# SCH_usb-hub_2025-07-15.net
KiCad netlist of a schematic drawn in EasyEDA
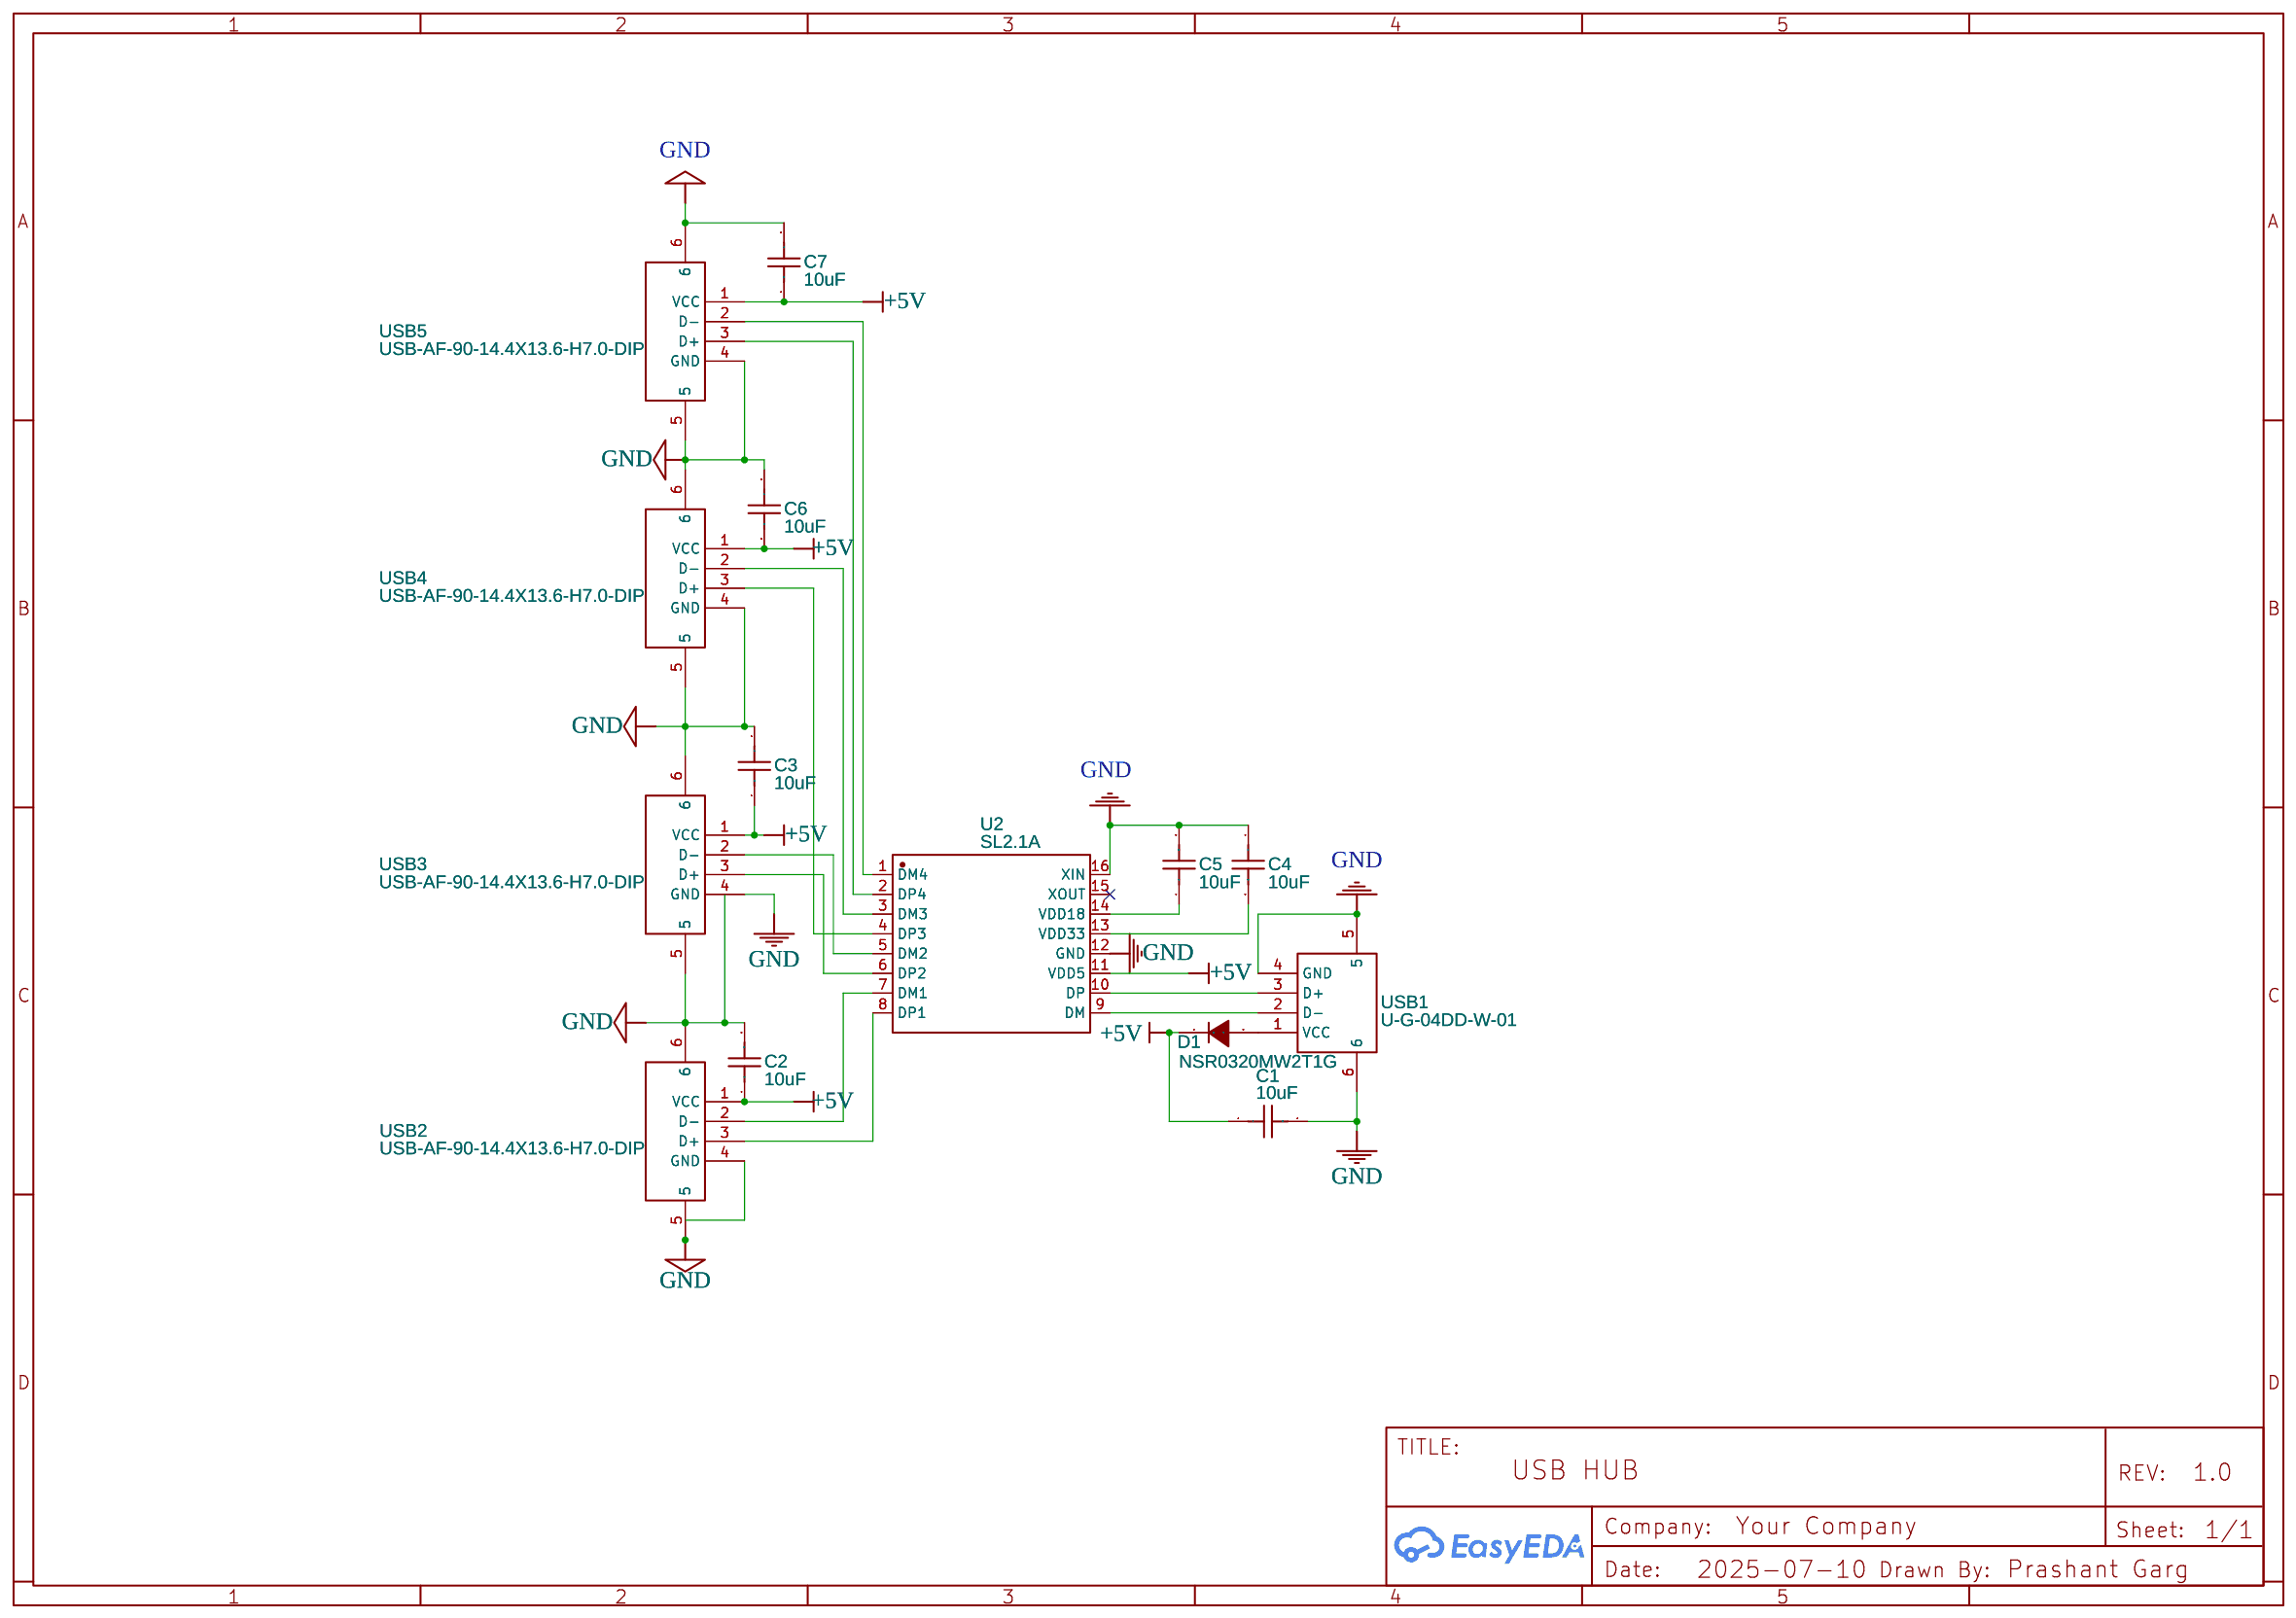
[diagram p0: schematic sheet]

(export (version "E")
  (design (tool "Eeschema 10.0.6"))
  (components
    (comp (ref "C1")
      (value "10uF")
      (fields
        (field (name "Manufacturer Part") "CL10A106KP8NNNC")
        (field (name "Manufacturer") "SAMSUNG(三星)")
      )
      (libsource (lib "") (part "CL10A106KP8NNNC_1"))
    )
    (comp (ref "C2")
      (value "10uF")
      (fields
        (field (name "Manufacturer Part") "CL10A106KP8NNNC")
        (field (name "Manufacturer") "SAMSUNG(三星)")
      )
      (libsource (lib "") (part "CL10A106KP8NNNC"))
    )
    (comp (ref "C3")
      (value "10uF")
      (fields
        (field (name "Manufacturer Part") "CL10A106KP8NNNC")
        (field (name "Manufacturer") "SAMSUNG(三星)")
      )
      (libsource (lib "") (part "CL10A106KP8NNNC"))
    )
    (comp (ref "C4")
      (value "10uF")
      (fields
        (field (name "Manufacturer Part") "CL10A106KP8NNNC")
        (field (name "Manufacturer") "SAMSUNG(三星)")
      )
      (libsource (lib "") (part "CL10A106KP8NNNC_2"))
    )
    (comp (ref "C5")
      (value "10uF")
      (fields
        (field (name "Manufacturer Part") "CL10A106KP8NNNC")
        (field (name "Manufacturer") "SAMSUNG(三星)")
      )
      (libsource (lib "") (part "CL10A106KP8NNNC"))
    )
    (comp (ref "C6")
      (value "10uF")
      (fields
        (field (name "Manufacturer Part") "CL10A106KP8NNNC")
        (field (name "Manufacturer") "SAMSUNG(三星)")
      )
      (libsource (lib "") (part "CL10A106KP8NNNC"))
    )
    (comp (ref "C7")
      (value "10uF")
      (fields
        (field (name "Manufacturer Part") "CL10A106KP8NNNC")
        (field (name "Manufacturer") "SAMSUNG(三星)")
      )
      (libsource (lib "") (part "CL10A106KP8NNNC"))
    )
    (comp (ref "D1")
      (value "NSR0320MW2T1G")
      (fields (field (name "Manufacturer") "onsemi(安森美)"))
      (libsource (lib "") (part "NSR0320MW2T1G"))
    )
    (comp (ref "U2")
      (value "SL2.1A")
      (fields (field (name "Manufacturer") "CoreChips(和芯润德)"))
      (libsource (lib "") (part "SL2.1A"))
    )
    (comp (ref "USB1")
      (value "U-G-04DD-W-01")
      (fields (field (name "Manufacturer Part") "U-G-O4DD-W-1") (field (name "Manufacturer") "韩国韩荣"))
      (libsource (lib "") (part "U-G-04DD-W-01"))
    )
    (comp (ref "USB2")
      (value "USB-AF-90-14.4X13.6-H7.0-DIP")
      (fields (field (name "Manufacturer Part") "903-131A1011D10100") (field (name "Manufacturer") "精拓金"))
      (libsource (lib "") (part "USB-AF-90-14.4X13.6-H7.0-DIP"))
    )
    (comp (ref "USB3")
      (value "USB-AF-90-14.4X13.6-H7.0-DIP")
      (fields (field (name "Manufacturer Part") "903-131A1011D10100") (field (name "Manufacturer") "精拓金"))
      (libsource (lib "") (part "USB-AF-90-14.4X13.6-H7.0-DIP"))
    )
    (comp (ref "USB4")
      (value "USB-AF-90-14.4X13.6-H7.0-DIP")
      (fields (field (name "Manufacturer Part") "903-131A1011D10100") (field (name "Manufacturer") "精拓金"))
      (libsource (lib "") (part "USB-AF-90-14.4X13.6-H7.0-DIP"))
    )
    (comp (ref "USB5")
      (value "USB-AF-90-14.4X13.6-H7.0-DIP")
      (fields (field (name "Manufacturer Part") "903-131A1011D10100") (field (name "Manufacturer") "精拓金"))
      (libsource (lib "") (part "USB-AF-90-14.4X13.6-H7.0-DIP"))
    )
  )
  (nets
    (net (code "1") (name "+5V") (class "Default")
      (node (ref "C1") (pin "1") (pinfunction "1_1") (pintype "unspecified"))
      (node (ref "C2") (pin "1") (pinfunction "1_1") (pintype "unspecified"))
      (node (ref "C3") (pin "1") (pinfunction "1_1") (pintype "unspecified"))
      (node (ref "C6") (pin "1") (pinfunction "1_1") (pintype "unspecified"))
      (node (ref "C7") (pin "1") (pinfunction "1_1") (pintype "unspecified"))
      (node (ref "D1") (pin "1") (pinfunction "C_1") (pintype "unspecified"))
      (node (ref "U2") (pin "11") (pinfunction "VDD5_11") (pintype "unspecified"))
      (node (ref "USB2") (pin "1") (pinfunction "VCC_1") (pintype "unspecified"))
      (node (ref "USB3") (pin "1") (pinfunction "VCC_1") (pintype "unspecified"))
      (node (ref "USB4") (pin "1") (pinfunction "VCC_1") (pintype "unspecified"))
      (node (ref "USB5") (pin "1") (pinfunction "VCC_1") (pintype "unspecified"))
    )
    (net (code "2") (name "GND") (class "Default")
      (node (ref "C1") (pin "2") (pinfunction "2_2") (pintype "unspecified"))
      (node (ref "C2") (pin "2") (pinfunction "2_2") (pintype "unspecified"))
      (node (ref "C3") (pin "2") (pinfunction "2_2") (pintype "unspecified"))
      (node (ref "C4") (pin "1") (pinfunction "1_1") (pintype "unspecified"))
      (node (ref "C5") (pin "2") (pinfunction "2_2") (pintype "unspecified"))
      (node (ref "C6") (pin "2") (pinfunction "2_2") (pintype "unspecified"))
      (node (ref "C7") (pin "2") (pinfunction "2_2") (pintype "unspecified"))
      (node (ref "U2") (pin "12") (pinfunction "GND_12") (pintype "unspecified"))
      (node (ref "U2") (pin "16") (pinfunction "XIN_16") (pintype "unspecified"))
      (node (ref "USB1") (pin "4") (pinfunction "GND_4") (pintype "unspecified"))
      (node (ref "USB1") (pin "5") (pinfunction "5_5") (pintype "unspecified"))
      (node (ref "USB1") (pin "6") (pinfunction "6_6") (pintype "unspecified"))
      (node (ref "USB2") (pin "4") (pinfunction "GND_4") (pintype "unspecified"))
      (node (ref "USB2") (pin "5") (pinfunction "5_5") (pintype "unspecified"))
      (node (ref "USB2") (pin "6") (pinfunction "6_6") (pintype "unspecified"))
      (node (ref "USB3") (pin "4") (pinfunction "GND_4") (pintype "unspecified"))
      (node (ref "USB3") (pin "5") (pinfunction "5_5") (pintype "unspecified"))
      (node (ref "USB3") (pin "6") (pinfunction "6_6") (pintype "unspecified"))
      (node (ref "USB4") (pin "4") (pinfunction "GND_4") (pintype "unspecified"))
      (node (ref "USB4") (pin "5") (pinfunction "5_5") (pintype "unspecified"))
      (node (ref "USB4") (pin "6") (pinfunction "6_6") (pintype "unspecified"))
      (node (ref "USB5") (pin "4") (pinfunction "GND_4") (pintype "unspecified"))
      (node (ref "USB5") (pin "5") (pinfunction "5_5") (pintype "unspecified"))
      (node (ref "USB5") (pin "6") (pinfunction "6_6") (pintype "unspecified"))
    )
    (net (code "3") (name "Net-(D1-A)") (class "Default")
      (node (ref "D1") (pin "2") (pinfunction "A_2") (pintype "unspecified"))
      (node (ref "USB1") (pin "1") (pinfunction "VCC_1") (pintype "unspecified"))
    )
    (net (code "4") (name "Net-(U2-DM)") (class "Default")
      (node (ref "U2") (pin "9") (pinfunction "DM_9") (pintype "unspecified"))
      (node (ref "USB1") (pin "2") (pinfunction "D-_2") (pintype "unspecified"))
    )
    (net (code "5") (name "Net-(U2-DM1)") (class "Default")
      (node (ref "U2") (pin "7") (pinfunction "DM1_7") (pintype "unspecified"))
      (node (ref "USB2") (pin "2") (pinfunction "D-_2") (pintype "unspecified"))
    )
    (net (code "6") (name "Net-(U2-DM2)") (class "Default")
      (node (ref "U2") (pin "5") (pinfunction "DM2_5") (pintype "unspecified"))
      (node (ref "USB3") (pin "2") (pinfunction "D-_2") (pintype "unspecified"))
    )
    (net (code "7") (name "Net-(U2-DM3)") (class "Default")
      (node (ref "U2") (pin "3") (pinfunction "DM3_3") (pintype "unspecified"))
      (node (ref "USB4") (pin "2") (pinfunction "D-_2") (pintype "unspecified"))
    )
    (net (code "8") (name "Net-(U2-DM4)") (class "Default")
      (node (ref "U2") (pin "1") (pinfunction "DM4_1") (pintype "unspecified"))
      (node (ref "USB5") (pin "2") (pinfunction "D-_2") (pintype "unspecified"))
    )
    (net (code "9") (name "Net-(U2-DP)") (class "Default")
      (node (ref "U2") (pin "10") (pinfunction "DP_10") (pintype "unspecified"))
      (node (ref "USB1") (pin "3") (pinfunction "D+_3") (pintype "unspecified"))
    )
    (net (code "10") (name "Net-(U2-DP1)") (class "Default")
      (node (ref "U2") (pin "8") (pinfunction "DP1_8") (pintype "unspecified"))
      (node (ref "USB2") (pin "3") (pinfunction "D+_3") (pintype "unspecified"))
    )
    (net (code "11") (name "Net-(U2-DP2)") (class "Default")
      (node (ref "U2") (pin "6") (pinfunction "DP2_6") (pintype "unspecified"))
      (node (ref "USB3") (pin "3") (pinfunction "D+_3") (pintype "unspecified"))
    )
    (net (code "12") (name "Net-(U2-DP3)") (class "Default")
      (node (ref "U2") (pin "4") (pinfunction "DP3_4") (pintype "unspecified"))
      (node (ref "USB4") (pin "3") (pinfunction "D+_3") (pintype "unspecified"))
    )
    (net (code "13") (name "Net-(U2-DP4)") (class "Default")
      (node (ref "U2") (pin "2") (pinfunction "DP4_2") (pintype "unspecified"))
      (node (ref "USB5") (pin "3") (pinfunction "D+_3") (pintype "unspecified"))
    )
    (net (code "14") (name "Net-(U2-VDD18)") (class "Default")
      (node (ref "C5") (pin "1") (pinfunction "1_1") (pintype "unspecified"))
      (node (ref "U2") (pin "14") (pinfunction "VDD18_14") (pintype "unspecified"))
    )
    (net (code "15") (name "Net-(U2-VDD33)") (class "Default")
      (node (ref "C4") (pin "2") (pinfunction "2_2") (pintype "unspecified"))
      (node (ref "U2") (pin "13") (pinfunction "VDD33_13") (pintype "unspecified"))
    )
    (net (code "16") (name "unconnected-(U2-XOUT-Pad15)") (class "Default")
      (node (ref "U2") (pin "15") (pinfunction "XOUT_15") (pintype "unspecified+no_connect"))
    )
  )
)
